# RevolvingStageController.net
KiCad netlist of a schematic drawn in Altium Designer
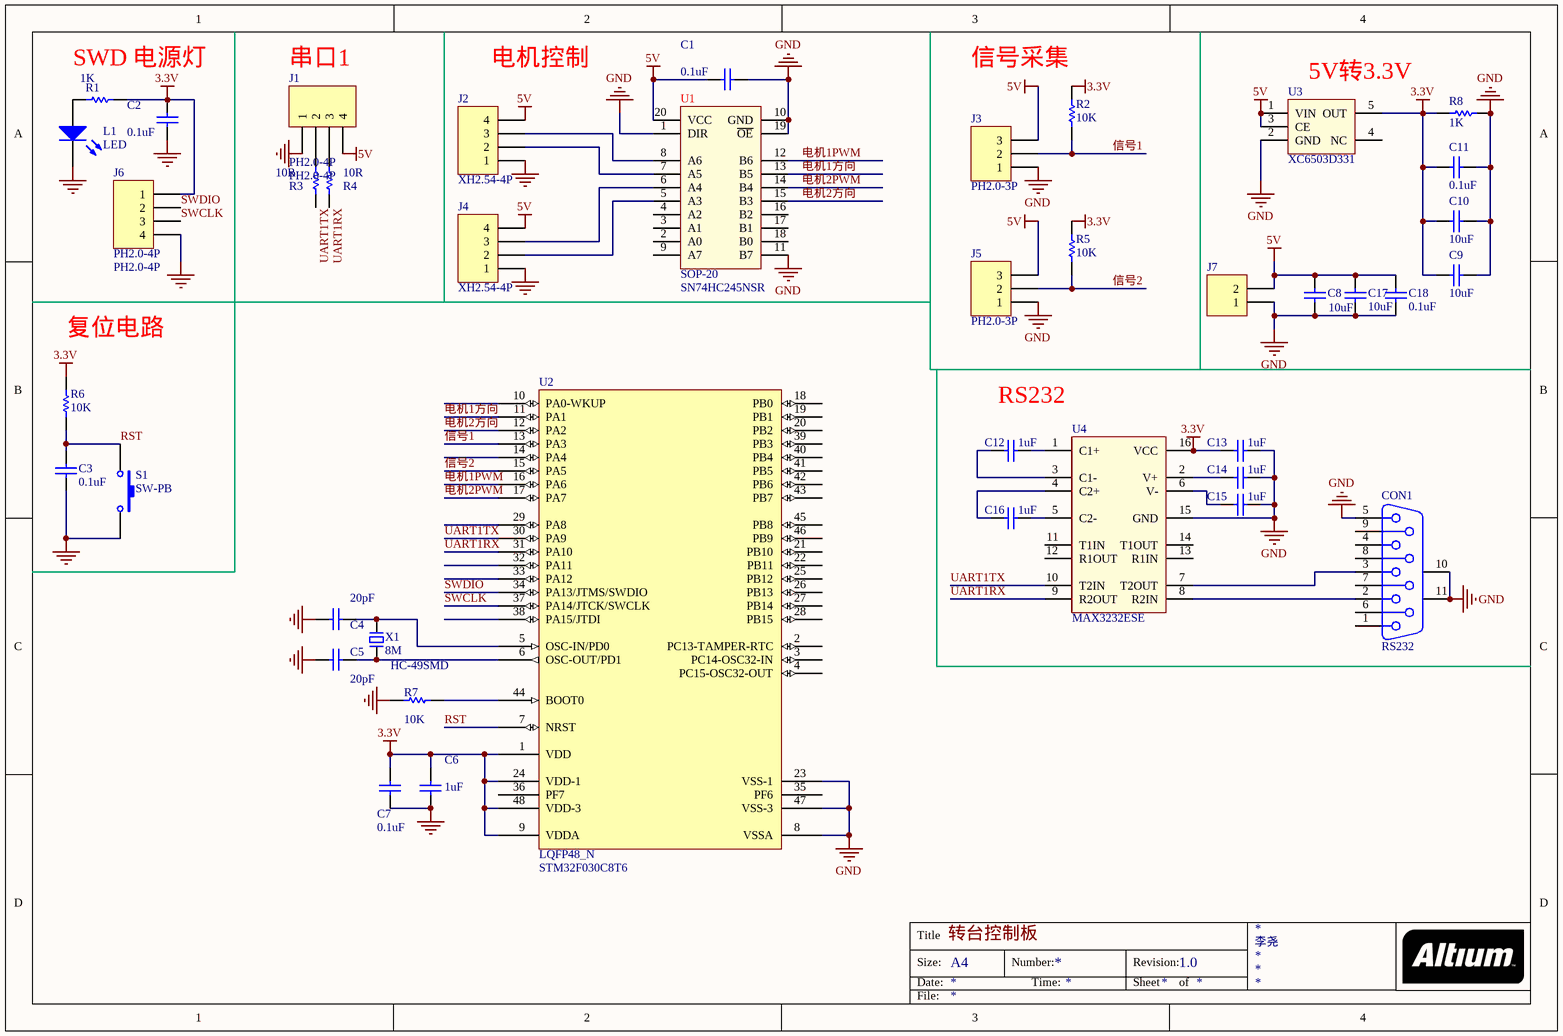
[diagram p0: RevolvingStageController.SchDoc]

(export (version "E")
  (design (tool "Eeschema 10.0.6"))
  (components
    (comp (ref "C1")
      (value "0.1uF")
      (footprint "0603")
      (description "Capacitor")
      (fields (field (name "PUBLISHER") "Altium Limited"))
      (libsource (lib "Miscellaneous Devices") (part "Cap"))
    )
    (comp (ref "C2")
      (value "0.1uF")
      (footprint "0603")
      (description "Capacitor")
      (fields (field (name "PUBLISHER") "Altium Limited"))
      (libsource (lib "Miscellaneous Devices") (part "Cap"))
    )
    (comp (ref "C3")
      (value "0.1uF")
      (footprint "0603")
      (description "Capacitor")
      (fields (field (name "PUBLISHER") "Altium Limited"))
      (libsource (lib "Miscellaneous Devices") (part "Cap"))
    )
    (comp (ref "C4")
      (value "20pF")
      (footprint "0603")
      (description "Capacitor")
      (fields (field (name "PUBLISHER") "Altium Limited"))
      (libsource (lib "Miscellaneous Devices") (part "Cap"))
    )
    (comp (ref "C5")
      (value "20pF")
      (footprint "0603")
      (description "Capacitor")
      (fields (field (name "PUBLISHER") "Altium Limited"))
      (libsource (lib "Miscellaneous Devices") (part "Cap"))
    )
    (comp (ref "C6")
      (value "1uF")
      (footprint "0603")
      (description "Capacitor")
      (fields (field (name "PUBLISHER") "Altium Limited"))
      (libsource (lib "Miscellaneous Devices") (part "Cap"))
    )
    (comp (ref "C7")
      (value "0.1uF")
      (footprint "0603")
      (description "Capacitor")
      (fields (field (name "PUBLISHER") "Altium Limited"))
      (libsource (lib "Miscellaneous Devices") (part "Cap"))
    )
    (comp (ref "C8")
      (value "10uF")
      (footprint "0603")
      (description "Capacitor")
      (fields (field (name "PUBLISHER") "Altium Limited"))
      (libsource (lib "Miscellaneous Devices") (part "Cap"))
    )
    (comp (ref "C9")
      (value "10uF")
      (footprint "0603")
      (description "Capacitor")
      (fields (field (name "PUBLISHER") "Altium Limited"))
      (libsource (lib "Miscellaneous Devices") (part "Cap"))
    )
    (comp (ref "C10")
      (value "10uF")
      (footprint "0603")
      (description "Capacitor")
      (fields (field (name "PUBLISHER") "Altium Limited"))
      (libsource (lib "Miscellaneous Devices") (part "Cap"))
    )
    (comp (ref "C11")
      (value "0.1uF")
      (footprint "0603")
      (description "Capacitor")
      (fields (field (name "PUBLISHER") "Altium Limited"))
      (libsource (lib "Miscellaneous Devices") (part "Cap"))
    )
    (comp (ref "C12")
      (value "1uF")
      (footprint "LiyaoPCB库:0603")
      (description "Capacitor")
      (fields (field (name "PUBLISHER") "Altium Limited"))
      (libsource (lib "Miscellaneous Devices") (part "Cap"))
    )
    (comp (ref "C13")
      (value "1uF")
      (footprint "0603")
      (description "Capacitor")
      (fields (field (name "PUBLISHER") "Altium Limited"))
      (libsource (lib "Miscellaneous Devices") (part "Cap"))
    )
    (comp (ref "C14")
      (value "1uF")
      (footprint "0603")
      (description "Capacitor")
      (fields (field (name "PUBLISHER") "Altium Limited"))
      (libsource (lib "Miscellaneous Devices") (part "Cap"))
    )
    (comp (ref "C15")
      (value "1uF")
      (footprint "0603")
      (description "Capacitor")
      (fields (field (name "PUBLISHER") "Altium Limited"))
      (libsource (lib "Miscellaneous Devices") (part "Cap"))
    )
    (comp (ref "C16")
      (value "1uF")
      (footprint "0603")
      (description "Capacitor")
      (fields (field (name "PUBLISHER") "Altium Limited"))
      (libsource (lib "Miscellaneous Devices") (part "Cap"))
    )
    (comp (ref "C17")
      (value "10uF")
      (footprint "0603")
      (description "电容0603")
      (fields (field (name "PUBLISHER") "Altium Limited"))
      (libsource (lib "Liyao原理图库") (part "Cap"))
    )
    (comp (ref "C18")
      (value "0.1uF")
      (footprint "0603")
      (description "电容0603")
      (fields (field (name "PUBLISHER") "Altium Limited"))
      (libsource (lib "Liyao原理图库") (part "Cap"))
    )
    (comp (ref "CON1")
      (value "RS232")
      (footprint "DSUB1.385-2H9-M")
      (description "Receptacle Assembly, 9 Position, Right Angle")
      (fields (field (name "PUBLISHER") "Altium Limited"))
      (libsource (lib "Liyao原理图库") (part "D Connector 9"))
    )
    (comp (ref "J1")
      (value "PH2.0-4P")
      (footprint "PH2.0-4P")
      (description "Header, 4-Pin")
      (fields (field (name "ALTIUM_VALUE") "PH2.0-4P") (field (name "PUBLISHER") "Altium Limited"))
      (libsource (lib "") (part "Header 4_2"))
    )
    (comp (ref "J2")
      (value "XH2.54-4P")
      (footprint "XH2.54-4")
      (description "Header, 4-Pin")
      (fields (field (name "PUBLISHER") "Altium Limited"))
      (libsource (lib "Miscellaneous Connectors") (part "Header 4"))
    )
    (comp (ref "J3")
      (value "PH2.0-3P")
      (footprint "PH2.0-3P")
      (description "Header, 3-Pin")
      (fields (field (name "PUBLISHER") "Altium Limited"))
      (libsource (lib "Sparks") (part "Header 3"))
    )
    (comp (ref "J4")
      (value "XH2.54-4P")
      (footprint "XH2.54-4")
      (description "Header, 4-Pin")
      (fields (field (name "PUBLISHER") "Altium Limited"))
      (libsource (lib "Miscellaneous Connectors") (part "Header 4"))
    )
    (comp (ref "J5")
      (value "PH2.0-3P")
      (footprint "PH2.0-3P")
      (description "Header, 3-Pin")
      (fields (field (name "PUBLISHER") "Altium Limited"))
      (libsource (lib "Sparks") (part "Header 3"))
    )
    (comp (ref "J6")
      (value "PH2.0-4P")
      (footprint "PH2.0-4P")
      (description "Header, 4-Pin")
      (fields (field (name "ALTIUM_VALUE") "PH2.0-4P") (field (name "PUBLISHER") "Altium Limited"))
      (libsource (lib "") (part "Header 4_1"))
    )
    (comp (ref "J7")
      (value "PH2.0-2P")
      (footprint "PH2.0-2P")
      (description "插座PH2.0-2P")
      (fields (field (name "PUBLISHER") "Altium Limited"))
      (libsource (lib "Liyao原理图库") (part "PH2.0-2P"))
    )
    (comp (ref "L1") (value "LED") (footprint "0603") (libsource (lib "Sparks") (part "LED")))
    (comp (ref "R1")
      (value "1K")
      (footprint "0603")
      (description "Resistor")
      (fields (field (name "PUBLISHER") "Altium Limited"))
      (libsource (lib "Miscellaneous Devices") (part "Res1"))
    )
    (comp (ref "R2")
      (value "10K")
      (footprint "0603")
      (description "Resistor")
      (fields (field (name "PUBLISHER") "Altium Limited"))
      (libsource (lib "Miscellaneous Devices") (part "Res1"))
    )
    (comp (ref "R3")
      (value "10R")
      (footprint "0603")
      (description "Resistor")
      (fields (field (name "PUBLISHER") "Altium Limited"))
      (libsource (lib "Miscellaneous Devices") (part "Res1"))
    )
    (comp (ref "R4")
      (value "10R")
      (footprint "0603")
      (description "Resistor")
      (fields (field (name "PUBLISHER") "Altium Limited"))
      (libsource (lib "Miscellaneous Devices") (part "Res1"))
    )
    (comp (ref "R5")
      (value "10K")
      (footprint "0603")
      (description "Resistor")
      (fields (field (name "PUBLISHER") "Altium Limited"))
      (libsource (lib "Miscellaneous Devices") (part "Res1"))
    )
    (comp (ref "R6")
      (value "10K")
      (footprint "0603")
      (description "Resistor")
      (fields (field (name "PUBLISHER") "Altium Limited"))
      (libsource (lib "Miscellaneous Devices") (part "Res1"))
    )
    (comp (ref "R7")
      (value "10K")
      (footprint "0603")
      (description "Resistor")
      (fields (field (name "PUBLISHER") "Altium Limited"))
      (libsource (lib "Miscellaneous Devices") (part "Res1"))
    )
    (comp (ref "R8")
      (value "1K")
      (footprint "0603")
      (description "Resistor")
      (fields (field (name "PUBLISHER") "Altium Limited"))
      (libsource (lib "Miscellaneous Devices") (part "Res1"))
    )
    (comp (ref "S1")
      (value "SW-PB")
      (footprint "SW-KEY")
      (description "Switch")
      (fields (field (name "PUBLISHER") "Altium Limited"))
      (libsource (lib "Miscellaneous Devices") (part "SW-PB"))
    )
    (comp (ref "U1")
      (value "SOP-20")
      (footprint "SOP-20")
      (fields (field (name "ALTIUM_VALUE") "SN74HC245NSR"))
      (libsource (lib "SCH") (part "74HC245"))
    )
    (comp (ref "U2")
      (value "LQFP48_N")
      (footprint "LQFP48_N")
      (description "STM32 ARM-based 32-bit MCU with 64 Kbytes Flash, 48-pin LQFP, Industrial Temperature")
      (fields (field (name "ALTIUM_VALUE") "STM32F030C8T6") (field (name "PUBLISHER") "*"))
      (libsource (lib "Liyao原理图库") (part "STM32F030C8T6"))
    )
    (comp (ref "U3")
      (value "XC6503D331")
      (footprint "SOT23-5")
      (libsource (lib "CYSchlib") (part "XC6503Dxxx"))
    )
    (comp (ref "U4")
      (value "MAX3232ESE")
      (footprint "SOIC-16N")
      (libsource (lib "Liyao原理图库") (part "MAX3232"))
    )
    (comp (ref "X1")
      (value "8M")
      (footprint "HC-49SMD")
      (fields (field (name "ALTIUM_VALUE") "HC-49SMD"))
      (libsource (lib "CYSchlib") (part "XTAL"))
    )
  )
  (nets
    (net (code "1") (name "/RST") (class "Default")
      (node (ref "C3") (pin "1") (pinfunction "1_1") (pintype "passive"))
      (node (ref "R6") (pin "2") (pinfunction "2_2") (pintype "passive"))
      (node (ref "S1") (pin "1") (pinfunction "1_1") (pintype "passive"))
      (node (ref "U2") (pin "7") (pinfunction "NRST_7") (pintype "bidirectional"))
    )
    (net (code "2") (name "/SWCLK") (class "Default")
      (node (ref "J6") (pin "3") (pinfunction "3_3") (pintype "passive"))
      (node (ref "U2") (pin "37") (pinfunction "PA14/JTCK/SWCLK_37") (pintype "bidirectional"))
    )
    (net (code "3") (name "/SWDIO") (class "Default")
      (node (ref "J6") (pin "2") (pinfunction "2_2") (pintype "passive"))
      (node (ref "U2") (pin "34") (pinfunction "PA13/JTMS/SWDIO_34") (pintype "bidirectional"))
    )
    (net (code "4") (name "/UART1RX") (class "Default")
      (node (ref "R4") (pin "2") (pinfunction "2_2") (pintype "passive"))
      (node (ref "U2") (pin "31") (pinfunction "PA10_31") (pintype "bidirectional"))
      (node (ref "U4") (pin "9") (pinfunction "R2OUT_9") (pintype "passive"))
    )
    (net (code "5") (name "/UART1TX") (class "Default")
      (node (ref "R3") (pin "2") (pinfunction "2_2") (pintype "passive"))
      (node (ref "U2") (pin "30") (pinfunction "PA9_30") (pintype "bidirectional"))
      (node (ref "U4") (pin "10") (pinfunction "T2IN_10") (pintype "passive"))
    )
    (net (code "6") (name "/信号1") (class "Default")
      (node (ref "J3") (pin "2") (pinfunction "2_2") (pintype "passive"))
      (node (ref "R2") (pin "2") (pinfunction "2_2") (pintype "passive"))
      (node (ref "U2") (pin "13") (pinfunction "PA3_13") (pintype "bidirectional"))
    )
    (net (code "7") (name "/信号2") (class "Default")
      (node (ref "J5") (pin "2") (pinfunction "2_2") (pintype "passive"))
      (node (ref "R5") (pin "2") (pinfunction "2_2") (pintype "passive"))
      (node (ref "U2") (pin "15") (pinfunction "PA5_15") (pintype "bidirectional"))
    )
    (net (code "8") (name "/电机1PWM") (class "Default")
      (node (ref "U1") (pin "12") (pinfunction "B6_12") (pintype "passive"))
      (node (ref "U2") (pin "16") (pinfunction "PA6_16") (pintype "bidirectional"))
    )
    (net (code "9") (name "/电机1方向") (class "Default")
      (node (ref "U1") (pin "13") (pinfunction "B5_13") (pintype "passive"))
      (node (ref "U2") (pin "11") (pinfunction "PA1_11") (pintype "bidirectional"))
    )
    (net (code "10") (name "/电机2PWM") (class "Default")
      (node (ref "U1") (pin "14") (pinfunction "B4_14") (pintype "passive"))
      (node (ref "U2") (pin "17") (pinfunction "PA7_17") (pintype "bidirectional"))
    )
    (net (code "11") (name "/电机2方向") (class "Default")
      (node (ref "U1") (pin "15") (pinfunction "B3_15") (pintype "passive"))
      (node (ref "U2") (pin "12") (pinfunction "PA2_12") (pintype "bidirectional"))
    )
    (net (code "12") (name "3.3V") (class "Default")
      (node (ref "C10") (pin "2") (pinfunction "2_2") (pintype "passive"))
      (node (ref "C11") (pin "2") (pinfunction "2_2") (pintype "passive"))
      (node (ref "C13") (pin "2") (pinfunction "2_2") (pintype "passive"))
      (node (ref "C2") (pin "1") (pinfunction "1_1") (pintype "passive"))
      (node (ref "C6") (pin "1") (pinfunction "1_1") (pintype "passive"))
      (node (ref "C7") (pin "1") (pinfunction "1_1") (pintype "passive"))
      (node (ref "C9") (pin "1") (pinfunction "1_1") (pintype "passive"))
      (node (ref "J6") (pin "1") (pinfunction "1_1") (pintype "passive"))
      (node (ref "R1") (pin "2") (pinfunction "2_2") (pintype "passive"))
      (node (ref "R2") (pin "1") (pinfunction "1_1") (pintype "passive"))
      (node (ref "R5") (pin "1") (pinfunction "1_1") (pintype "passive"))
      (node (ref "R6") (pin "1") (pinfunction "1_1") (pintype "passive"))
      (node (ref "R8") (pin "2") (pinfunction "2_2") (pintype "passive"))
      (node (ref "U2") (pin "1") (pinfunction "VDD_1") (pintype "power_in"))
      (node (ref "U2") (pin "24") (pinfunction "VDD-1_24") (pintype "power_in"))
      (node (ref "U2") (pin "48") (pinfunction "VDD-3_48") (pintype "power_in"))
      (node (ref "U2") (pin "9") (pinfunction "VDDA_9") (pintype "power_in"))
      (node (ref "U3") (pin "5") (pinfunction "OUT_5") (pintype "passive"))
      (node (ref "U4") (pin "16") (pinfunction "VCC_16") (pintype "passive"))
    )
    (net (code "13") (name "5V") (class "Default")
      (node (ref "C1") (pin "1") (pinfunction "1_1") (pintype "passive"))
      (node (ref "C17") (pin "2") (pinfunction "2_2") (pintype "passive"))
      (node (ref "C18") (pin "2") (pinfunction "2_2") (pintype "passive"))
      (node (ref "C8") (pin "2") (pinfunction "2_2") (pintype "passive"))
      (node (ref "J1") (pin "4") (pinfunction "4_4") (pintype "passive"))
      (node (ref "J2") (pin "4") (pinfunction "4_4") (pintype "passive"))
      (node (ref "J3") (pin "3") (pinfunction "3_3") (pintype "passive"))
      (node (ref "J4") (pin "4") (pinfunction "4_4") (pintype "passive"))
      (node (ref "J5") (pin "3") (pinfunction "3_3") (pintype "passive"))
      (node (ref "J7") (pin "2") (pinfunction "2_2") (pintype "passive"))
      (node (ref "U1") (pin "20") (pinfunction "VCC_20") (pintype "passive"))
      (node (ref "U3") (pin "1") (pinfunction "VIN_1") (pintype "passive"))
      (node (ref "U3") (pin "3") (pinfunction "CE_3") (pintype "passive"))
    )
    (net (code "14") (name "GND") (class "Default")
      (node (ref "C1") (pin "2") (pinfunction "2_2") (pintype "passive"))
      (node (ref "C10") (pin "1") (pinfunction "1_1") (pintype "passive"))
      (node (ref "C11") (pin "1") (pinfunction "1_1") (pintype "passive"))
      (node (ref "C13") (pin "1") (pinfunction "1_1") (pintype "passive"))
      (node (ref "C14") (pin "1") (pinfunction "1_1") (pintype "passive"))
      (node (ref "C15") (pin "1") (pinfunction "1_1") (pintype "passive"))
      (node (ref "C17") (pin "1") (pinfunction "1_1") (pintype "passive"))
      (node (ref "C18") (pin "1") (pinfunction "1_1") (pintype "passive"))
      (node (ref "C2") (pin "2") (pinfunction "2_2") (pintype "passive"))
      (node (ref "C3") (pin "2") (pinfunction "2_2") (pintype "passive"))
      (node (ref "C4") (pin "1") (pinfunction "1_1") (pintype "passive"))
      (node (ref "C5") (pin "1") (pinfunction "1_1") (pintype "passive"))
      (node (ref "C6") (pin "2") (pinfunction "2_2") (pintype "passive"))
      (node (ref "C7") (pin "2") (pinfunction "2_2") (pintype "passive"))
      (node (ref "C8") (pin "1") (pinfunction "1_1") (pintype "passive"))
      (node (ref "C9") (pin "2") (pinfunction "2_2") (pintype "passive"))
      (node (ref "CON1") (pin "10") (pinfunction "MH1_10") (pintype "passive"))
      (node (ref "CON1") (pin "11") (pinfunction "MH2_11") (pintype "passive"))
      (node (ref "CON1") (pin "5") (pinfunction "5_5") (pintype "passive"))
      (node (ref "J1") (pin "1") (pinfunction "1_1") (pintype "passive"))
      (node (ref "J2") (pin "1") (pinfunction "1_1") (pintype "passive"))
      (node (ref "J3") (pin "1") (pinfunction "1_1") (pintype "passive"))
      (node (ref "J4") (pin "1") (pinfunction "1_1") (pintype "passive"))
      (node (ref "J5") (pin "1") (pinfunction "1_1") (pintype "passive"))
      (node (ref "J6") (pin "4") (pinfunction "4_4") (pintype "passive"))
      (node (ref "J7") (pin "1") (pinfunction "1_1") (pintype "passive"))
      (node (ref "L1") (pin "2") (pinfunction "K_2") (pintype "passive"))
      (node (ref "R7") (pin "1") (pinfunction "1_1") (pintype "passive"))
      (node (ref "R8") (pin "1") (pinfunction "1_1") (pintype "passive"))
      (node (ref "S1") (pin "2") (pinfunction "2_2") (pintype "passive"))
      (node (ref "U1") (pin "1") (pinfunction "DIR_1") (pintype "passive"))
      (node (ref "U1") (pin "10") (pinfunction "GND_10") (pintype "passive"))
      (node (ref "U1") (pin "11") (pinfunction "B7_11") (pintype "passive"))
      (node (ref "U1") (pin "19") (pinfunction "~{OE}_19") (pintype "passive"))
      (node (ref "U2") (pin "23") (pinfunction "VSS-1_23") (pintype "power_in"))
      (node (ref "U2") (pin "47") (pinfunction "VSS-3_47") (pintype "power_in"))
      (node (ref "U2") (pin "8") (pinfunction "VSSA_8") (pintype "power_in"))
      (node (ref "U3") (pin "2") (pinfunction "GND_2") (pintype "passive"))
      (node (ref "U4") (pin "15") (pinfunction "GND_15") (pintype "passive"))
    )
    (net (code "15") (name "Net-(J1-Pad2)") (class "Default")
      (node (ref "J1") (pin "2") (pinfunction "2_2") (pintype "passive"))
      (node (ref "R3") (pin "1") (pinfunction "1_1") (pintype "passive"))
    )
    (net (code "16") (name "Net-(J1-Pad3)") (class "Default")
      (node (ref "J1") (pin "3") (pinfunction "3_3") (pintype "passive"))
      (node (ref "R4") (pin "1") (pinfunction "1_1") (pintype "passive"))
    )
    (net (code "17") (name "Net-(L1-A)") (class "Default")
      (node (ref "L1") (pin "1") (pinfunction "A_1") (pintype "passive"))
      (node (ref "R1") (pin "1") (pinfunction "1_1") (pintype "passive"))
    )
    (net (code "18") (name "Net-(U1-A3)") (class "Default")
      (node (ref "J4") (pin "2") (pinfunction "2_2") (pintype "passive"))
      (node (ref "U1") (pin "5") (pinfunction "A3_5") (pintype "passive"))
    )
    (net (code "19") (name "Net-(U1-A4)") (class "Default")
      (node (ref "J4") (pin "3") (pinfunction "3_3") (pintype "passive"))
      (node (ref "U1") (pin "6") (pinfunction "A4_6") (pintype "passive"))
    )
    (net (code "20") (name "Net-(U1-A5)") (class "Default")
      (node (ref "J2") (pin "2") (pinfunction "2_2") (pintype "passive"))
      (node (ref "U1") (pin "7") (pinfunction "A5_7") (pintype "passive"))
    )
    (net (code "21") (name "Net-(U1-A6)") (class "Default")
      (node (ref "J2") (pin "3") (pinfunction "3_3") (pintype "passive"))
      (node (ref "U1") (pin "8") (pinfunction "A6_8") (pintype "passive"))
    )
    (net (code "22") (name "Net-(U2-BOOT0)") (class "Default")
      (node (ref "R7") (pin "2") (pinfunction "2_2") (pintype "passive"))
      (node (ref "U2") (pin "44") (pinfunction "BOOT0_44") (pintype "input"))
    )
    (net (code "23") (name "Net-(U2-OSC-IN{slash}PD0)") (class "Default")
      (node (ref "C4") (pin "2") (pinfunction "2_2") (pintype "passive"))
      (node (ref "U2") (pin "5") (pinfunction "OSC-IN/PD0_5") (pintype "input"))
      (node (ref "X1") (pin "2") (pinfunction "2_2") (pintype "passive"))
    )
    (net (code "24") (name "Net-(U2-OSC-OUT{slash}PD1)") (class "Default")
      (node (ref "C5") (pin "2") (pinfunction "2_2") (pintype "passive"))
      (node (ref "U2") (pin "6") (pinfunction "OSC-OUT/PD1_6") (pintype "output"))
      (node (ref "X1") (pin "1") (pinfunction "1_1") (pintype "passive"))
    )
    (net (code "25") (name "Net-(U4-C1+)") (class "Default")
      (node (ref "C12") (pin "1") (pinfunction "1_1") (pintype "passive"))
      (node (ref "U4") (pin "1") (pinfunction "C1+_1") (pintype "passive"))
    )
    (net (code "26") (name "Net-(U4-C1-)") (class "Default")
      (node (ref "C12") (pin "2") (pinfunction "2_2") (pintype "passive"))
      (node (ref "U4") (pin "3") (pinfunction "C1-_3") (pintype "passive"))
    )
    (net (code "27") (name "Net-(U4-C2+)") (class "Default")
      (node (ref "C16") (pin "2") (pinfunction "2_2") (pintype "passive"))
      (node (ref "U4") (pin "4") (pinfunction "C2+_4") (pintype "passive"))
    )
    (net (code "28") (name "Net-(U4-C2-)") (class "Default")
      (node (ref "C16") (pin "1") (pinfunction "1_1") (pintype "passive"))
      (node (ref "U4") (pin "5") (pinfunction "C2-_5") (pintype "passive"))
    )
    (net (code "29") (name "Net-(U4-R2IN)") (class "Default")
      (node (ref "CON1") (pin "2") (pinfunction "2_2") (pintype "passive"))
      (node (ref "U4") (pin "8") (pinfunction "R2IN_8") (pintype "passive"))
    )
    (net (code "30") (name "Net-(U4-T2OUT)") (class "Default")
      (node (ref "CON1") (pin "3") (pinfunction "3_3") (pintype "passive"))
      (node (ref "U4") (pin "7") (pinfunction "T2OUT_7") (pintype "passive"))
    )
    (net (code "31") (name "Net-(U4-V+)") (class "Default")
      (node (ref "C14") (pin "2") (pinfunction "2_2") (pintype "passive"))
      (node (ref "U4") (pin "2") (pinfunction "V+_2") (pintype "passive"))
    )
    (net (code "32") (name "Net-(U4-V-)") (class "Default")
      (node (ref "C15") (pin "2") (pinfunction "2_2") (pintype "passive"))
      (node (ref "U4") (pin "6") (pinfunction "V-_6") (pintype "passive"))
    )
    (net (code "33") (name "unconnected-(CON1-Pad1)") (class "Default")
      (node (ref "CON1") (pin "1") (pinfunction "1_1") (pintype "passive"))
    )
    (net (code "34") (name "unconnected-(CON1-Pad4)") (class "Default")
      (node (ref "CON1") (pin "4") (pinfunction "4_4") (pintype "passive"))
    )
    (net (code "35") (name "unconnected-(CON1-Pad6)") (class "Default")
      (node (ref "CON1") (pin "6") (pinfunction "6_6") (pintype "passive"))
    )
    (net (code "36") (name "unconnected-(CON1-Pad7)") (class "Default")
      (node (ref "CON1") (pin "7") (pinfunction "7_7") (pintype "passive"))
    )
    (net (code "37") (name "unconnected-(CON1-Pad8)") (class "Default")
      (node (ref "CON1") (pin "8") (pinfunction "8_8") (pintype "passive"))
    )
    (net (code "38") (name "unconnected-(CON1-Pad9)") (class "Default")
      (node (ref "CON1") (pin "9") (pinfunction "9_9") (pintype "passive"))
    )
    (net (code "39") (name "unconnected-(U1-A0-Pad2)") (class "Default")
      (node (ref "U1") (pin "2") (pinfunction "A0_2") (pintype "passive"))
    )
    (net (code "40") (name "unconnected-(U1-A1-Pad3)") (class "Default")
      (node (ref "U1") (pin "3") (pinfunction "A1_3") (pintype "passive"))
    )
    (net (code "41") (name "unconnected-(U1-A2-Pad4)") (class "Default")
      (node (ref "U1") (pin "4") (pinfunction "A2_4") (pintype "passive"))
    )
    (net (code "42") (name "unconnected-(U1-A7-Pad9)") (class "Default")
      (node (ref "U1") (pin "9") (pinfunction "A7_9") (pintype "passive"))
    )
    (net (code "43") (name "unconnected-(U1-B0-Pad18)") (class "Default")
      (node (ref "U1") (pin "18") (pinfunction "B0_18") (pintype "passive"))
    )
    (net (code "44") (name "unconnected-(U1-B1-Pad17)") (class "Default")
      (node (ref "U1") (pin "17") (pinfunction "B1_17") (pintype "passive"))
    )
    (net (code "45") (name "unconnected-(U1-B2-Pad16)") (class "Default")
      (node (ref "U1") (pin "16") (pinfunction "B2_16") (pintype "passive"))
    )
    (net (code "46") (name "unconnected-(U2-PA0-WKUP-Pad10)") (class "Default")
      (node (ref "U2") (pin "10") (pinfunction "PA0-WKUP_10") (pintype "bidirectional"))
    )
    (net (code "47") (name "unconnected-(U2-PA4-Pad14)") (class "Default")
      (node (ref "U2") (pin "14") (pinfunction "PA4_14") (pintype "bidirectional"))
    )
    (net (code "48") (name "unconnected-(U2-PA8-Pad29)") (class "Default")
      (node (ref "U2") (pin "29") (pinfunction "PA8_29") (pintype "bidirectional"))
    )
    (net (code "49") (name "unconnected-(U2-PA11-Pad32)") (class "Default")
      (node (ref "U2") (pin "32") (pinfunction "PA11_32") (pintype "bidirectional"))
    )
    (net (code "50") (name "unconnected-(U2-PA12-Pad33)") (class "Default")
      (node (ref "U2") (pin "33") (pinfunction "PA12_33") (pintype "bidirectional"))
    )
    (net (code "51") (name "unconnected-(U2-PA15{slash}JTDI-Pad38)") (class "Default")
      (node (ref "U2") (pin "38") (pinfunction "PA15/JTDI_38") (pintype "bidirectional"))
    )
    (net (code "52") (name "unconnected-(U2-PB0-Pad18)") (class "Default")
      (node (ref "U2") (pin "18") (pinfunction "PB0_18") (pintype "bidirectional"))
    )
    (net (code "53") (name "unconnected-(U2-PB1-Pad19)") (class "Default")
      (node (ref "U2") (pin "19") (pinfunction "PB1_19") (pintype "bidirectional"))
    )
    (net (code "54") (name "unconnected-(U2-PB2-Pad20)") (class "Default")
      (node (ref "U2") (pin "20") (pinfunction "PB2_20") (pintype "bidirectional"))
    )
    (net (code "55") (name "unconnected-(U2-PB3-Pad39)") (class "Default")
      (node (ref "U2") (pin "39") (pinfunction "PB3_39") (pintype "bidirectional"))
    )
    (net (code "56") (name "unconnected-(U2-PB4-Pad40)") (class "Default")
      (node (ref "U2") (pin "40") (pinfunction "PB4_40") (pintype "bidirectional"))
    )
    (net (code "57") (name "unconnected-(U2-PB5-Pad41)") (class "Default")
      (node (ref "U2") (pin "41") (pinfunction "PB5_41") (pintype "bidirectional"))
    )
    (net (code "58") (name "unconnected-(U2-PB6-Pad42)") (class "Default")
      (node (ref "U2") (pin "42") (pinfunction "PB6_42") (pintype "bidirectional"))
    )
    (net (code "59") (name "unconnected-(U2-PB7-Pad43)") (class "Default")
      (node (ref "U2") (pin "43") (pinfunction "PB7_43") (pintype "bidirectional"))
    )
    (net (code "60") (name "unconnected-(U2-PB8-Pad45)") (class "Default")
      (node (ref "U2") (pin "45") (pinfunction "PB8_45") (pintype "bidirectional"))
    )
    (net (code "61") (name "unconnected-(U2-PB9-Pad46)") (class "Default")
      (node (ref "U2") (pin "46") (pinfunction "PB9_46") (pintype "bidirectional"))
    )
    (net (code "62") (name "unconnected-(U2-PB10-Pad21)") (class "Default")
      (node (ref "U2") (pin "21") (pinfunction "PB10_21") (pintype "bidirectional"))
    )
    (net (code "63") (name "unconnected-(U2-PB11-Pad22)") (class "Default")
      (node (ref "U2") (pin "22") (pinfunction "PB11_22") (pintype "bidirectional"))
    )
    (net (code "64") (name "unconnected-(U2-PB12-Pad25)") (class "Default")
      (node (ref "U2") (pin "25") (pinfunction "PB12_25") (pintype "bidirectional"))
    )
    (net (code "65") (name "unconnected-(U2-PB13-Pad26)") (class "Default")
      (node (ref "U2") (pin "26") (pinfunction "PB13_26") (pintype "bidirectional"))
    )
    (net (code "66") (name "unconnected-(U2-PB14-Pad27)") (class "Default")
      (node (ref "U2") (pin "27") (pinfunction "PB14_27") (pintype "bidirectional"))
    )
    (net (code "67") (name "unconnected-(U2-PB15-Pad28)") (class "Default")
      (node (ref "U2") (pin "28") (pinfunction "PB15_28") (pintype "bidirectional"))
    )
    (net (code "68") (name "unconnected-(U2-PC13-TAMPER-RTC-Pad2)") (class "Default")
      (node (ref "U2") (pin "2") (pinfunction "PC13-TAMPER-RTC_2") (pintype "bidirectional"))
    )
    (net (code "69") (name "unconnected-(U2-PC14-OSC32-IN-Pad3)") (class "Default")
      (node (ref "U2") (pin "3") (pinfunction "PC14-OSC32-IN_3") (pintype "bidirectional"))
    )
    (net (code "70") (name "unconnected-(U2-PC15-OSC32-OUT-Pad4)") (class "Default")
      (node (ref "U2") (pin "4") (pinfunction "PC15-OSC32-OUT_4") (pintype "bidirectional"))
    )
    (net (code "71") (name "unconnected-(U2-PF6-Pad35)") (class "Default")
      (node (ref "U2") (pin "35") (pinfunction "PF6_35") (pintype "power_in"))
    )
    (net (code "72") (name "unconnected-(U2-PF7-Pad36)") (class "Default")
      (node (ref "U2") (pin "36") (pinfunction "PF7_36") (pintype "power_in"))
    )
    (net (code "73") (name "unconnected-(U3-NC-Pad4)") (class "Default")
      (node (ref "U3") (pin "4") (pinfunction "NC_4") (pintype "passive"))
    )
    (net (code "74") (name "unconnected-(U4-R1IN-Pad13)") (class "Default")
      (node (ref "U4") (pin "13") (pinfunction "R1IN_13") (pintype "passive"))
    )
    (net (code "75") (name "unconnected-(U4-R1OUT-Pad12)") (class "Default")
      (node (ref "U4") (pin "12") (pinfunction "R1OUT_12") (pintype "passive"))
    )
    (net (code "76") (name "unconnected-(U4-T1IN-Pad11)") (class "Default")
      (node (ref "U4") (pin "11") (pinfunction "T1IN_11") (pintype "passive"))
    )
    (net (code "77") (name "unconnected-(U4-T1OUT-Pad14)") (class "Default")
      (node (ref "U4") (pin "14") (pinfunction "T1OUT_14") (pintype "passive"))
    )
  )
)
